# SCH_ADE-Final_2024-05-14.net
KiCad netlist of a schematic drawn in EasyEDA
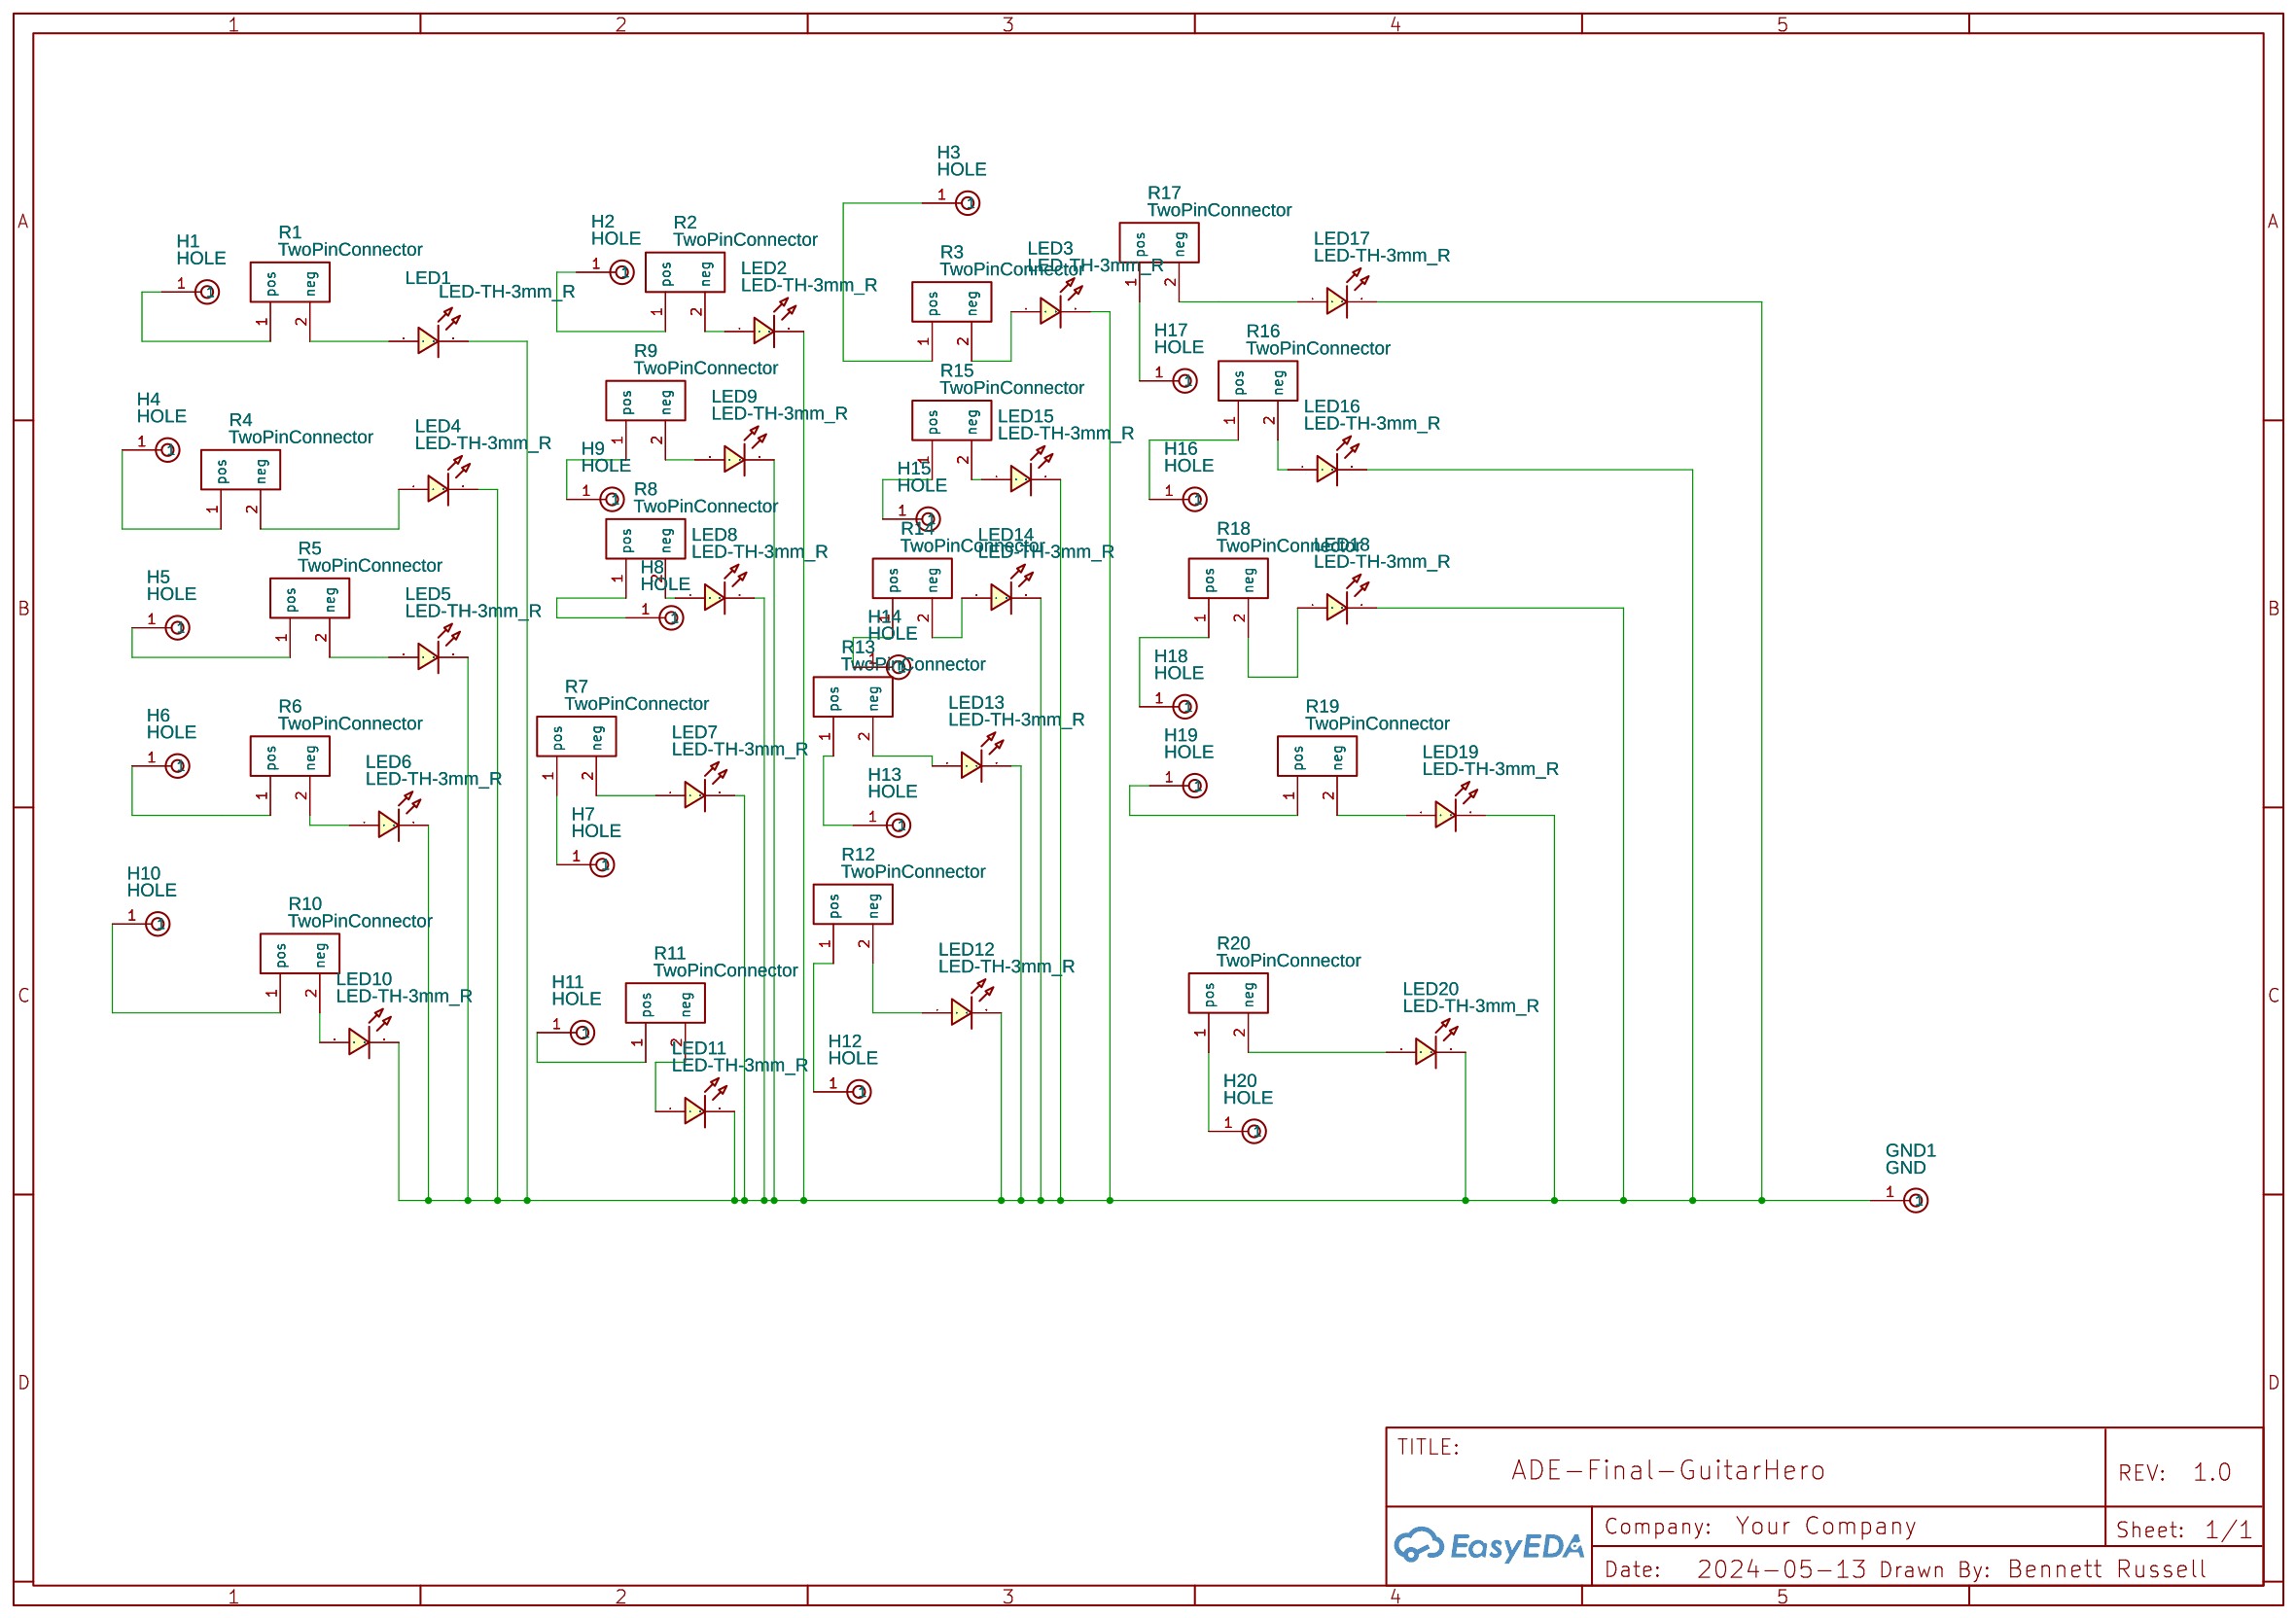
[diagram p0: schematic sheet]

(export (version "E")
  (design (tool "Eeschema 10.0.6"))
  (components
    (comp (ref "GND1") (value "GND") (libsource (lib "") (part "HOLE_1")))
    (comp (ref "H1") (value "HOLE") (libsource (lib "") (part "HOLE")))
    (comp (ref "H2") (value "HOLE") (libsource (lib "") (part "HOLE")))
    (comp (ref "H3") (value "HOLE") (libsource (lib "") (part "HOLE")))
    (comp (ref "H4") (value "HOLE") (libsource (lib "") (part "HOLE")))
    (comp (ref "H5") (value "HOLE") (libsource (lib "") (part "HOLE")))
    (comp (ref "H6") (value "HOLE") (libsource (lib "") (part "HOLE")))
    (comp (ref "H7") (value "HOLE") (libsource (lib "") (part "HOLE")))
    (comp (ref "H8") (value "HOLE") (libsource (lib "") (part "HOLE")))
    (comp (ref "H9") (value "HOLE") (libsource (lib "") (part "HOLE")))
    (comp (ref "H10") (value "HOLE") (libsource (lib "") (part "HOLE")))
    (comp (ref "H11") (value "HOLE") (libsource (lib "") (part "HOLE")))
    (comp (ref "H12") (value "HOLE") (libsource (lib "") (part "HOLE")))
    (comp (ref "H13") (value "HOLE") (libsource (lib "") (part "HOLE")))
    (comp (ref "H14") (value "HOLE") (libsource (lib "") (part "HOLE")))
    (comp (ref "H15") (value "HOLE") (libsource (lib "") (part "HOLE")))
    (comp (ref "H16") (value "HOLE") (libsource (lib "") (part "HOLE")))
    (comp (ref "H17") (value "HOLE") (libsource (lib "") (part "HOLE")))
    (comp (ref "H18") (value "HOLE") (libsource (lib "") (part "HOLE")))
    (comp (ref "H19") (value "HOLE") (libsource (lib "") (part "HOLE")))
    (comp (ref "H20") (value "HOLE") (libsource (lib "") (part "HOLE")))
    (comp (ref "LED1")
      (value "LED-TH-3mm_R")
      (fields
        (field (name "Manufacturer Part") "204-10SDRD/S530-A3-L")
        (field (name "Manufacturer") "EVERLIGHT(台湾亿光)")
      )
      (libsource (lib "") (part "LED-TH-3mm_R"))
    )
    (comp (ref "LED2")
      (value "LED-TH-3mm_R")
      (fields
        (field (name "Manufacturer Part") "204-10SDRD/S530-A3-L")
        (field (name "Manufacturer") "EVERLIGHT(台湾亿光)")
      )
      (libsource (lib "") (part "LED-TH-3mm_R"))
    )
    (comp (ref "LED3")
      (value "LED-TH-3mm_R")
      (fields
        (field (name "Manufacturer Part") "204-10SDRD/S530-A3-L")
        (field (name "Manufacturer") "EVERLIGHT(台湾亿光)")
      )
      (libsource (lib "") (part "LED-TH-3mm_R"))
    )
    (comp (ref "LED4")
      (value "LED-TH-3mm_R")
      (fields
        (field (name "Manufacturer Part") "204-10SDRD/S530-A3-L")
        (field (name "Manufacturer") "EVERLIGHT(台湾亿光)")
      )
      (libsource (lib "") (part "LED-TH-3mm_R"))
    )
    (comp (ref "LED5")
      (value "LED-TH-3mm_R")
      (fields
        (field (name "Manufacturer Part") "204-10SDRD/S530-A3-L")
        (field (name "Manufacturer") "EVERLIGHT(台湾亿光)")
      )
      (libsource (lib "") (part "LED-TH-3mm_R"))
    )
    (comp (ref "LED6")
      (value "LED-TH-3mm_R")
      (fields
        (field (name "Manufacturer Part") "204-10SDRD/S530-A3-L")
        (field (name "Manufacturer") "EVERLIGHT(台湾亿光)")
      )
      (libsource (lib "") (part "LED-TH-3mm_R"))
    )
    (comp (ref "LED7")
      (value "LED-TH-3mm_R")
      (fields
        (field (name "Manufacturer Part") "204-10SDRD/S530-A3-L")
        (field (name "Manufacturer") "EVERLIGHT(台湾亿光)")
      )
      (libsource (lib "") (part "LED-TH-3mm_R"))
    )
    (comp (ref "LED8")
      (value "LED-TH-3mm_R")
      (fields
        (field (name "Manufacturer Part") "204-10SDRD/S530-A3-L")
        (field (name "Manufacturer") "EVERLIGHT(台湾亿光)")
      )
      (libsource (lib "") (part "LED-TH-3mm_R"))
    )
    (comp (ref "LED9")
      (value "LED-TH-3mm_R")
      (fields
        (field (name "Manufacturer Part") "204-10SDRD/S530-A3-L")
        (field (name "Manufacturer") "EVERLIGHT(台湾亿光)")
      )
      (libsource (lib "") (part "LED-TH-3mm_R"))
    )
    (comp (ref "LED10")
      (value "LED-TH-3mm_R")
      (fields
        (field (name "Manufacturer Part") "204-10SDRD/S530-A3-L")
        (field (name "Manufacturer") "EVERLIGHT(台湾亿光)")
      )
      (libsource (lib "") (part "LED-TH-3mm_R"))
    )
    (comp (ref "LED11")
      (value "LED-TH-3mm_R")
      (fields
        (field (name "Manufacturer Part") "204-10SDRD/S530-A3-L")
        (field (name "Manufacturer") "EVERLIGHT(台湾亿光)")
      )
      (libsource (lib "") (part "LED-TH-3mm_R"))
    )
    (comp (ref "LED12")
      (value "LED-TH-3mm_R")
      (fields
        (field (name "Manufacturer Part") "204-10SDRD/S530-A3-L")
        (field (name "Manufacturer") "EVERLIGHT(台湾亿光)")
      )
      (libsource (lib "") (part "LED-TH-3mm_R"))
    )
    (comp (ref "LED13")
      (value "LED-TH-3mm_R")
      (fields
        (field (name "Manufacturer Part") "204-10SDRD/S530-A3-L")
        (field (name "Manufacturer") "EVERLIGHT(台湾亿光)")
      )
      (libsource (lib "") (part "LED-TH-3mm_R"))
    )
    (comp (ref "LED14")
      (value "LED-TH-3mm_R")
      (fields
        (field (name "Manufacturer Part") "204-10SDRD/S530-A3-L")
        (field (name "Manufacturer") "EVERLIGHT(台湾亿光)")
      )
      (libsource (lib "") (part "LED-TH-3mm_R"))
    )
    (comp (ref "LED15")
      (value "LED-TH-3mm_R")
      (fields
        (field (name "Manufacturer Part") "204-10SDRD/S530-A3-L")
        (field (name "Manufacturer") "EVERLIGHT(台湾亿光)")
      )
      (libsource (lib "") (part "LED-TH-3mm_R"))
    )
    (comp (ref "LED16")
      (value "LED-TH-3mm_R")
      (fields
        (field (name "Manufacturer Part") "204-10SDRD/S530-A3-L")
        (field (name "Manufacturer") "EVERLIGHT(台湾亿光)")
      )
      (libsource (lib "") (part "LED-TH-3mm_R"))
    )
    (comp (ref "LED17")
      (value "LED-TH-3mm_R")
      (fields
        (field (name "Manufacturer Part") "204-10SDRD/S530-A3-L")
        (field (name "Manufacturer") "EVERLIGHT(台湾亿光)")
      )
      (libsource (lib "") (part "LED-TH-3mm_R"))
    )
    (comp (ref "LED18")
      (value "LED-TH-3mm_R")
      (fields
        (field (name "Manufacturer Part") "204-10SDRD/S530-A3-L")
        (field (name "Manufacturer") "EVERLIGHT(台湾亿光)")
      )
      (libsource (lib "") (part "LED-TH-3mm_R"))
    )
    (comp (ref "LED19")
      (value "LED-TH-3mm_R")
      (fields
        (field (name "Manufacturer Part") "204-10SDRD/S530-A3-L")
        (field (name "Manufacturer") "EVERLIGHT(台湾亿光)")
      )
      (libsource (lib "") (part "LED-TH-3mm_R"))
    )
    (comp (ref "LED20")
      (value "LED-TH-3mm_R")
      (fields
        (field (name "Manufacturer Part") "204-10SDRD/S530-A3-L")
        (field (name "Manufacturer") "EVERLIGHT(台湾亿光)")
      )
      (libsource (lib "") (part "LED-TH-3mm_R"))
    )
    (comp (ref "R1") (value "TwoPinConnector") (libsource (lib "") (part "TwoPinConnector")))
    (comp (ref "R2") (value "TwoPinConnector") (libsource (lib "") (part "TwoPinConnector")))
    (comp (ref "R3") (value "TwoPinConnector") (libsource (lib "") (part "TwoPinConnector")))
    (comp (ref "R4") (value "TwoPinConnector") (libsource (lib "") (part "TwoPinConnector")))
    (comp (ref "R5") (value "TwoPinConnector") (libsource (lib "") (part "TwoPinConnector")))
    (comp (ref "R6") (value "TwoPinConnector") (libsource (lib "") (part "TwoPinConnector")))
    (comp (ref "R7") (value "TwoPinConnector") (libsource (lib "") (part "TwoPinConnector")))
    (comp (ref "R8") (value "TwoPinConnector") (libsource (lib "") (part "TwoPinConnector")))
    (comp (ref "R9") (value "TwoPinConnector") (libsource (lib "") (part "TwoPinConnector")))
    (comp (ref "R10") (value "TwoPinConnector") (libsource (lib "") (part "TwoPinConnector")))
    (comp (ref "R11") (value "TwoPinConnector") (libsource (lib "") (part "TwoPinConnector")))
    (comp (ref "R12") (value "TwoPinConnector") (libsource (lib "") (part "TwoPinConnector")))
    (comp (ref "R13") (value "TwoPinConnector") (libsource (lib "") (part "TwoPinConnector")))
    (comp (ref "R14") (value "TwoPinConnector") (libsource (lib "") (part "TwoPinConnector")))
    (comp (ref "R15") (value "TwoPinConnector") (libsource (lib "") (part "TwoPinConnector")))
    (comp (ref "R16") (value "TwoPinConnector") (libsource (lib "") (part "TwoPinConnector")))
    (comp (ref "R17") (value "TwoPinConnector") (libsource (lib "") (part "TwoPinConnector")))
    (comp (ref "R18") (value "TwoPinConnector") (libsource (lib "") (part "TwoPinConnector")))
    (comp (ref "R19") (value "TwoPinConnector") (libsource (lib "") (part "TwoPinConnector")))
    (comp (ref "R20") (value "TwoPinConnector") (libsource (lib "") (part "TwoPinConnector")))
  )
  (nets
    (net (code "1") (name "Net-(GND1-Pad1)") (class "Default")
      (node (ref "GND1") (pin "1") (pinfunction "1_1") (pintype "unspecified"))
      (node (ref "LED1") (pin "2") (pinfunction "2_2") (pintype "unspecified"))
      (node (ref "LED10") (pin "2") (pinfunction "2_2") (pintype "unspecified"))
      (node (ref "LED11") (pin "2") (pinfunction "2_2") (pintype "unspecified"))
      (node (ref "LED12") (pin "2") (pinfunction "2_2") (pintype "unspecified"))
      (node (ref "LED13") (pin "2") (pinfunction "2_2") (pintype "unspecified"))
      (node (ref "LED14") (pin "2") (pinfunction "2_2") (pintype "unspecified"))
      (node (ref "LED15") (pin "2") (pinfunction "2_2") (pintype "unspecified"))
      (node (ref "LED16") (pin "2") (pinfunction "2_2") (pintype "unspecified"))
      (node (ref "LED17") (pin "2") (pinfunction "2_2") (pintype "unspecified"))
      (node (ref "LED18") (pin "2") (pinfunction "2_2") (pintype "unspecified"))
      (node (ref "LED19") (pin "2") (pinfunction "2_2") (pintype "unspecified"))
      (node (ref "LED2") (pin "2") (pinfunction "2_2") (pintype "unspecified"))
      (node (ref "LED20") (pin "2") (pinfunction "2_2") (pintype "unspecified"))
      (node (ref "LED3") (pin "2") (pinfunction "2_2") (pintype "unspecified"))
      (node (ref "LED4") (pin "2") (pinfunction "2_2") (pintype "unspecified"))
      (node (ref "LED5") (pin "2") (pinfunction "2_2") (pintype "unspecified"))
      (node (ref "LED6") (pin "2") (pinfunction "2_2") (pintype "unspecified"))
      (node (ref "LED7") (pin "2") (pinfunction "2_2") (pintype "unspecified"))
      (node (ref "LED8") (pin "2") (pinfunction "2_2") (pintype "unspecified"))
      (node (ref "LED9") (pin "2") (pinfunction "2_2") (pintype "unspecified"))
    )
    (net (code "2") (name "Net-(R1-neg)") (class "Default")
      (node (ref "LED1") (pin "1") (pinfunction "1_1") (pintype "unspecified"))
      (node (ref "R1") (pin "2") (pinfunction "neg_2") (pintype "unspecified"))
    )
    (net (code "3") (name "Net-(R1-pos)") (class "Default")
      (node (ref "H1") (pin "1") (pinfunction "1_1") (pintype "unspecified"))
      (node (ref "R1") (pin "1") (pinfunction "pos_1") (pintype "unspecified"))
    )
    (net (code "4") (name "Net-(R2-neg)") (class "Default")
      (node (ref "LED2") (pin "1") (pinfunction "1_1") (pintype "unspecified"))
      (node (ref "R2") (pin "2") (pinfunction "neg_2") (pintype "unspecified"))
    )
    (net (code "5") (name "Net-(R2-pos)") (class "Default")
      (node (ref "H2") (pin "1") (pinfunction "1_1") (pintype "unspecified"))
      (node (ref "R2") (pin "1") (pinfunction "pos_1") (pintype "unspecified"))
    )
    (net (code "6") (name "Net-(R3-neg)") (class "Default")
      (node (ref "LED3") (pin "1") (pinfunction "1_1") (pintype "unspecified"))
      (node (ref "R3") (pin "2") (pinfunction "neg_2") (pintype "unspecified"))
    )
    (net (code "7") (name "Net-(R3-pos)") (class "Default")
      (node (ref "H3") (pin "1") (pinfunction "1_1") (pintype "unspecified"))
      (node (ref "R3") (pin "1") (pinfunction "pos_1") (pintype "unspecified"))
    )
    (net (code "8") (name "Net-(R4-neg)") (class "Default")
      (node (ref "LED4") (pin "1") (pinfunction "1_1") (pintype "unspecified"))
      (node (ref "R4") (pin "2") (pinfunction "neg_2") (pintype "unspecified"))
    )
    (net (code "9") (name "Net-(R4-pos)") (class "Default")
      (node (ref "H4") (pin "1") (pinfunction "1_1") (pintype "unspecified"))
      (node (ref "R4") (pin "1") (pinfunction "pos_1") (pintype "unspecified"))
    )
    (net (code "10") (name "Net-(R5-neg)") (class "Default")
      (node (ref "LED5") (pin "1") (pinfunction "1_1") (pintype "unspecified"))
      (node (ref "R5") (pin "2") (pinfunction "neg_2") (pintype "unspecified"))
    )
    (net (code "11") (name "Net-(R5-pos)") (class "Default")
      (node (ref "H5") (pin "1") (pinfunction "1_1") (pintype "unspecified"))
      (node (ref "R5") (pin "1") (pinfunction "pos_1") (pintype "unspecified"))
    )
    (net (code "12") (name "Net-(R6-neg)") (class "Default")
      (node (ref "LED6") (pin "1") (pinfunction "1_1") (pintype "unspecified"))
      (node (ref "R6") (pin "2") (pinfunction "neg_2") (pintype "unspecified"))
    )
    (net (code "13") (name "Net-(R6-pos)") (class "Default")
      (node (ref "H6") (pin "1") (pinfunction "1_1") (pintype "unspecified"))
      (node (ref "R6") (pin "1") (pinfunction "pos_1") (pintype "unspecified"))
    )
    (net (code "14") (name "Net-(R7-neg)") (class "Default")
      (node (ref "LED7") (pin "1") (pinfunction "1_1") (pintype "unspecified"))
      (node (ref "R7") (pin "2") (pinfunction "neg_2") (pintype "unspecified"))
    )
    (net (code "15") (name "Net-(R7-pos)") (class "Default")
      (node (ref "H7") (pin "1") (pinfunction "1_1") (pintype "unspecified"))
      (node (ref "R7") (pin "1") (pinfunction "pos_1") (pintype "unspecified"))
    )
    (net (code "16") (name "Net-(R8-neg)") (class "Default")
      (node (ref "LED8") (pin "1") (pinfunction "1_1") (pintype "unspecified"))
      (node (ref "R8") (pin "2") (pinfunction "neg_2") (pintype "unspecified"))
    )
    (net (code "17") (name "Net-(R8-pos)") (class "Default")
      (node (ref "H8") (pin "1") (pinfunction "1_1") (pintype "unspecified"))
      (node (ref "R8") (pin "1") (pinfunction "pos_1") (pintype "unspecified"))
    )
    (net (code "18") (name "Net-(R9-neg)") (class "Default")
      (node (ref "LED9") (pin "1") (pinfunction "1_1") (pintype "unspecified"))
      (node (ref "R9") (pin "2") (pinfunction "neg_2") (pintype "unspecified"))
    )
    (net (code "19") (name "Net-(R9-pos)") (class "Default")
      (node (ref "H9") (pin "1") (pinfunction "1_1") (pintype "unspecified"))
      (node (ref "R9") (pin "1") (pinfunction "pos_1") (pintype "unspecified"))
    )
    (net (code "20") (name "Net-(R10-neg)") (class "Default")
      (node (ref "LED10") (pin "1") (pinfunction "1_1") (pintype "unspecified"))
      (node (ref "R10") (pin "2") (pinfunction "neg_2") (pintype "unspecified"))
    )
    (net (code "21") (name "Net-(R10-pos)") (class "Default")
      (node (ref "H10") (pin "1") (pinfunction "1_1") (pintype "unspecified"))
      (node (ref "R10") (pin "1") (pinfunction "pos_1") (pintype "unspecified"))
    )
    (net (code "22") (name "Net-(R11-neg)") (class "Default")
      (node (ref "LED11") (pin "1") (pinfunction "1_1") (pintype "unspecified"))
      (node (ref "R11") (pin "2") (pinfunction "neg_2") (pintype "unspecified"))
    )
    (net (code "23") (name "Net-(R11-pos)") (class "Default")
      (node (ref "H11") (pin "1") (pinfunction "1_1") (pintype "unspecified"))
      (node (ref "R11") (pin "1") (pinfunction "pos_1") (pintype "unspecified"))
    )
    (net (code "24") (name "Net-(R12-neg)") (class "Default")
      (node (ref "LED12") (pin "1") (pinfunction "1_1") (pintype "unspecified"))
      (node (ref "R12") (pin "2") (pinfunction "neg_2") (pintype "unspecified"))
    )
    (net (code "25") (name "Net-(R12-pos)") (class "Default")
      (node (ref "H12") (pin "1") (pinfunction "1_1") (pintype "unspecified"))
      (node (ref "R12") (pin "1") (pinfunction "pos_1") (pintype "unspecified"))
    )
    (net (code "26") (name "Net-(R13-neg)") (class "Default")
      (node (ref "LED13") (pin "1") (pinfunction "1_1") (pintype "unspecified"))
      (node (ref "R13") (pin "2") (pinfunction "neg_2") (pintype "unspecified"))
    )
    (net (code "27") (name "Net-(R13-pos)") (class "Default")
      (node (ref "H13") (pin "1") (pinfunction "1_1") (pintype "unspecified"))
      (node (ref "R13") (pin "1") (pinfunction "pos_1") (pintype "unspecified"))
    )
    (net (code "28") (name "Net-(R14-neg)") (class "Default")
      (node (ref "LED14") (pin "1") (pinfunction "1_1") (pintype "unspecified"))
      (node (ref "R14") (pin "2") (pinfunction "neg_2") (pintype "unspecified"))
    )
    (net (code "29") (name "Net-(R14-pos)") (class "Default")
      (node (ref "H14") (pin "1") (pinfunction "1_1") (pintype "unspecified"))
      (node (ref "R14") (pin "1") (pinfunction "pos_1") (pintype "unspecified"))
    )
    (net (code "30") (name "Net-(R15-neg)") (class "Default")
      (node (ref "LED15") (pin "1") (pinfunction "1_1") (pintype "unspecified"))
      (node (ref "R15") (pin "2") (pinfunction "neg_2") (pintype "unspecified"))
    )
    (net (code "31") (name "Net-(R15-pos)") (class "Default")
      (node (ref "H15") (pin "1") (pinfunction "1_1") (pintype "unspecified"))
      (node (ref "R15") (pin "1") (pinfunction "pos_1") (pintype "unspecified"))
    )
    (net (code "32") (name "Net-(R16-neg)") (class "Default")
      (node (ref "LED16") (pin "1") (pinfunction "1_1") (pintype "unspecified"))
      (node (ref "R16") (pin "2") (pinfunction "neg_2") (pintype "unspecified"))
    )
    (net (code "33") (name "Net-(R16-pos)") (class "Default")
      (node (ref "H16") (pin "1") (pinfunction "1_1") (pintype "unspecified"))
      (node (ref "R16") (pin "1") (pinfunction "pos_1") (pintype "unspecified"))
    )
    (net (code "34") (name "Net-(R17-neg)") (class "Default")
      (node (ref "LED17") (pin "1") (pinfunction "1_1") (pintype "unspecified"))
      (node (ref "R17") (pin "2") (pinfunction "neg_2") (pintype "unspecified"))
    )
    (net (code "35") (name "Net-(R17-pos)") (class "Default")
      (node (ref "H17") (pin "1") (pinfunction "1_1") (pintype "unspecified"))
      (node (ref "R17") (pin "1") (pinfunction "pos_1") (pintype "unspecified"))
    )
    (net (code "36") (name "Net-(R18-neg)") (class "Default")
      (node (ref "LED18") (pin "1") (pinfunction "1_1") (pintype "unspecified"))
      (node (ref "R18") (pin "2") (pinfunction "neg_2") (pintype "unspecified"))
    )
    (net (code "37") (name "Net-(R18-pos)") (class "Default")
      (node (ref "H18") (pin "1") (pinfunction "1_1") (pintype "unspecified"))
      (node (ref "R18") (pin "1") (pinfunction "pos_1") (pintype "unspecified"))
    )
    (net (code "38") (name "Net-(R19-neg)") (class "Default")
      (node (ref "LED19") (pin "1") (pinfunction "1_1") (pintype "unspecified"))
      (node (ref "R19") (pin "2") (pinfunction "neg_2") (pintype "unspecified"))
    )
    (net (code "39") (name "Net-(R19-pos)") (class "Default")
      (node (ref "H19") (pin "1") (pinfunction "1_1") (pintype "unspecified"))
      (node (ref "R19") (pin "1") (pinfunction "pos_1") (pintype "unspecified"))
    )
    (net (code "40") (name "Net-(R20-neg)") (class "Default")
      (node (ref "LED20") (pin "1") (pinfunction "1_1") (pintype "unspecified"))
      (node (ref "R20") (pin "2") (pinfunction "neg_2") (pintype "unspecified"))
    )
    (net (code "41") (name "Net-(R20-pos)") (class "Default")
      (node (ref "H20") (pin "1") (pinfunction "1_1") (pintype "unspecified"))
      (node (ref "R20") (pin "1") (pinfunction "pos_1") (pintype "unspecified"))
    )
  )
)
